# Power-Supply.net
KiCad netlist of a schematic drawn in Altium Designer
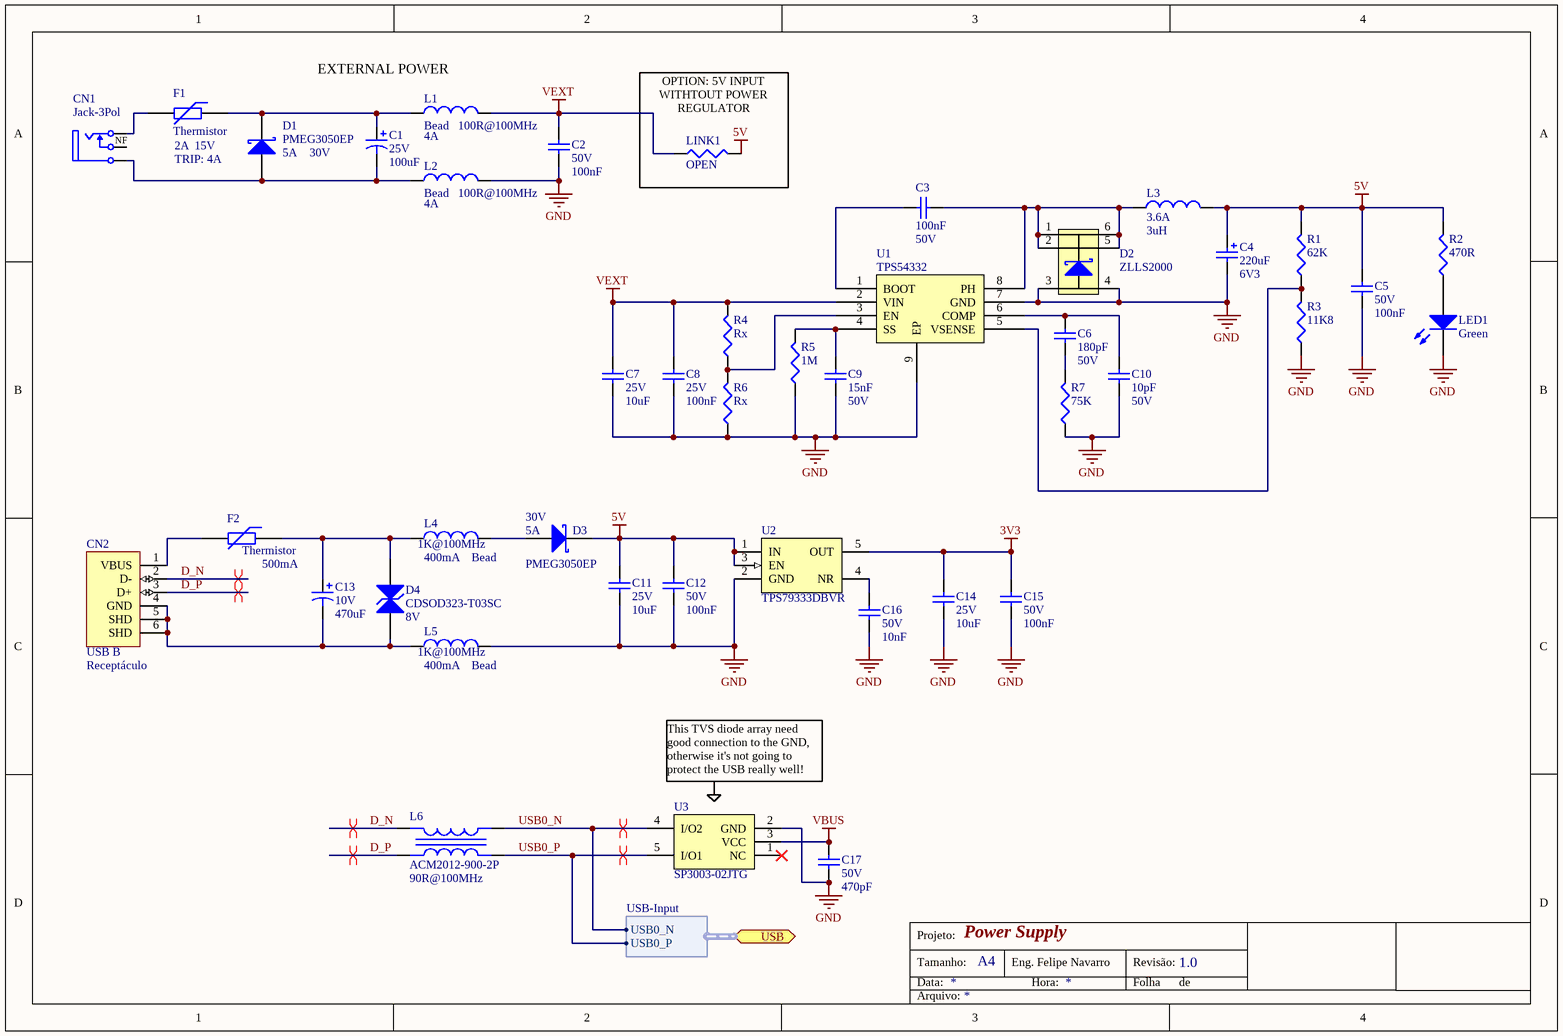
[diagram p0: Power-Supply.SchDoc]

(export (version "E")
  (design (tool "Eeschema 10.0.6"))
  (components
    (comp (ref "C1")
      (value "100uF")
      (footprint "CPOLRAD8X14")
      (description "Polarized Capacitor (Radial)")
      (fields (field (name "TENSÃO") "25V") (field (name "Comment") "Capacitor Eletrolítico"))
      (libsource (lib "NavarroCAP") (part "PCap 100uF 25V 8d.x14h."))
    )
    (comp (ref "C2")
      (value "100nF")
      (footprint "CC0603")
      (description "Capacitor (Semiconductor SIM Model)")
      (fields (field (name "TENSÃO") "50V") (field (name "Comment") "Capacitor Cerâmico"))
      (libsource (lib "NavarroCAP") (part "Cap 100nF 50V 0603 X7R"))
    )
    (comp (ref "C3")
      (value "100nF")
      (footprint "CC0603")
      (description "Capacitor (Semiconductor SIM Model)")
      (fields (field (name "TENSÃO") "50V") (field (name "Comment") "Capacitor Cerâmico"))
      (libsource (lib "NavarroCAP") (part "Cap 100nF 50V 0603 X7R"))
    )
    (comp (ref "C4")
      (value "220uF")
      (footprint "CPOL2917")
      (description "Polarized Capacitor")
      (fields (field (name "TENSÃO") "6V3") (field (name "Comment") "Capacitor Tântalo"))
      (libsource (lib "NavarroCAP") (part "PCap 220uF 6V3 2917 LOESR"))
    )
    (comp (ref "C5")
      (value "100nF")
      (footprint "CC0603")
      (description "Capacitor (Semiconductor SIM Model)")
      (fields (field (name "TENSÃO") "50V") (field (name "Comment") "Capacitor Cerâmico"))
      (libsource (lib "NavarroCAP") (part "Cap 100nF 50V 0603 X7R"))
    )
    (comp (ref "C6")
      (value "180pF")
      (footprint "CC0603")
      (description "Capacitor (Semiconductor SIM Model)")
      (fields (field (name "TENSÃO") "50V") (field (name "Comment") "Capacitor Cerâmico"))
      (libsource (lib "NavarroCAP") (part "Cap 180pF 50V 0603 NP0"))
    )
    (comp (ref "C7")
      (value "10uF")
      (footprint "CC0805")
      (description "Capacitor (Semiconductor SIM Model)")
      (fields (field (name "TENSÃO") "25V") (field (name "Comment") "Capacitor Cerâmico"))
      (libsource (lib "NavarroCAP") (part "Cap 10uF 25V 0805 X5R"))
    )
    (comp (ref "C8")
      (value "100nF")
      (footprint "CC0603")
      (description "Capacitor (Semiconductor SIM Model)")
      (fields (field (name "TENSÃO") "25V") (field (name "Comment") "Capacitor Cerâmico"))
      (libsource (lib "NavarroCAP") (part "Cap 100nF 25V 0603 X7R"))
    )
    (comp (ref "C9")
      (value "15nF")
      (footprint "CC0603")
      (description "Capacitor (Semiconductor SIM Model)")
      (fields (field (name "TENSÃO") "50V") (field (name "Comment") "Capacitor Cerâmico"))
      (libsource (lib "NavarroCAP") (part "Cap 15nF 50V 0603 X7R"))
    )
    (comp (ref "C10")
      (value "10pF")
      (footprint "CC0603")
      (description "Capacitor (Semiconductor SIM Model)")
      (fields (field (name "TENSÃO") "50V") (field (name "Comment") "Capacitor Cerâmico"))
      (libsource (lib "NavarroCAP") (part "Cap 10pF 50V 0603 NP0 5%"))
    )
    (comp (ref "C11")
      (value "10uF")
      (footprint "CC0805")
      (description "Capacitor (Semiconductor SIM Model)")
      (fields (field (name "TENSÃO") "25V") (field (name "Comment") "Capacitor Cerâmico"))
      (libsource (lib "NavarroCAP") (part "Cap 10uF 25V 0805 X5R"))
    )
    (comp (ref "C12")
      (value "100nF")
      (footprint "CC0603")
      (description "Capacitor (Semiconductor SIM Model)")
      (fields (field (name "TENSÃO") "50V") (field (name "Comment") "Capacitor Cerâmico"))
      (libsource (lib "NavarroCAP") (part "Cap 100nF 50V 0603 X7R"))
    )
    (comp (ref "C13")
      (value "470uF")
      (footprint "CPOLRAD6X12")
      (description "Polarized Capacitor (Radial)")
      (fields (field (name "TENSÃO") "10V") (field (name "Comment") "Capacitor Eletrolítico"))
      (libsource (lib "NavarroCAP") (part "PCap 470uF 10V 6d.x12h."))
    )
    (comp (ref "C14")
      (value "10uF")
      (footprint "CC0805")
      (description "Capacitor (Semiconductor SIM Model)")
      (fields (field (name "TENSÃO") "25V") (field (name "Comment") "Capacitor Cerâmico"))
      (libsource (lib "NavarroCAP") (part "Cap 10uF 25V 0805 X5R"))
    )
    (comp (ref "C15")
      (value "100nF")
      (footprint "CC0603")
      (description "Capacitor (Semiconductor SIM Model)")
      (fields (field (name "TENSÃO") "50V") (field (name "Comment") "Capacitor Cerâmico"))
      (libsource (lib "NavarroCAP") (part "Cap 100nF 50V 0603 X7R"))
    )
    (comp (ref "C16")
      (value "10nF")
      (footprint "CC0603")
      (description "Capacitor (Semiconductor SIM Model)")
      (fields (field (name "TENSÃO") "50V") (field (name "Comment") "Capacitor Cerâmico"))
      (libsource (lib "NavarroCAP") (part "Cap 10nF 50V 0603 X7R 5%"))
    )
    (comp (ref "C17")
      (value "470pF")
      (footprint "CC0603")
      (description "Capacitor (Semiconductor SIM Model)")
      (fields (field (name "TENSÃO") "50V") (field (name "Comment") "Capacitor Cerâmico"))
      (libsource (lib "NavarroCAP") (part "Cap 470pF 50V 0603 X7R"))
    )
    (comp (ref "CN1")
      (value "Jack-3Pol")
      (footprint "CONN_JACK-FONTE_3N")
      (description "Jack Socket, Thru-Hole, Vertical, 2 Conductors, 3 Contacts Single Switch, Normally Closed")
      (libsource (lib "NavarroCON") (part "Jack-3Pol"))
    )
    (comp (ref "CN2")
      (value "USB B")
      (footprint "CONN_USB-B_RCPT-H")
      (description "Conector Jack USB B, Through Hole, Right Angle, Horizontal")
      (fields (field (name "ALTIUM_VALUE") "Receptáculo"))
      (libsource (lib "NavarroCON") (part "USB B RCPT-H"))
    )
    (comp (ref "D1")
      (value "PMEG3050EP")
      (footprint "SOD-128")
      (description "Schottky Diode")
      (fields (field (name "CORRENTE") "5A") (field (name "TENSÃO") "30V"))
      (libsource (lib "NavarroSEMI") (part "DS 30V 5A SOD-128"))
    )
    (comp (ref "D2")
      (value "ZLLS2000")
      (footprint "SOT-23-6N")
      (description "Power Shottky")
      (libsource (lib "NavarroSEMI") (part "DPS 40V 2.2A SOT-23-6N"))
    )
    (comp (ref "D3")
      (value "PMEG3050EP")
      (footprint "SOD-128")
      (description "Schottky Diode")
      (fields (field (name "CORRENTE") "5A") (field (name "TENSÃO") "30V"))
      (libsource (lib "NavarroSEMI") (part "DS 30V 5A SOD-128"))
    )
    (comp (ref "D4")
      (value "CDSOD323-T03SC")
      (footprint "SOD-323 BIDIRECT")
      (description "Transient Voltage Supressor diode")
      (fields (field (name "TENSÃO") "8V"))
      (libsource (lib "NavarroSEMI") (part "TVS 8V 5% SOD323 BI 400W"))
    )
    (comp (ref "F1")
      (value "Thermistor")
      (footprint "CC1210")
      (description "Varistor (Voltage-Sensitive Resistor)")
      (fields (field (name "CORRENTE") "2A") (field (name "TENSÃO") "15V") (field (name "OBS") "TRIP: 4A"))
      (libsource (lib "Miscellaneous Devices") (part "Res Varistor"))
    )
    (comp (ref "F2")
      (value "Thermistor")
      (footprint "CC1812")
      (description "Varistor (Voltage-Sensitive Resistor)")
      (fields (field (name "CORRENTE") "500mA"))
      (libsource (lib "Miscellaneous Devices") (part "Res Varistor"))
    )
    (comp (ref "L1")
      (value "Bead")
      (footprint "CC0805")
      (fields (field (name "CORRENTE") "4A") (field (name "ALTIUM_VALUE") "100R@100MHz"))
      (libsource (lib "NavarroIND") (part "Bd 180R@100MHz 1806 3A"))
    )
    (comp (ref "L2")
      (value "Bead")
      (footprint "CC0805")
      (fields (field (name "CORRENTE") "4A") (field (name "ALTIUM_VALUE") "100R@100MHz"))
      (libsource (lib "NavarroIND") (part "Bd 180R@100MHz 1806 3A"))
    )
    (comp (ref "L3")
      (value "3uH")
      (footprint "NR2424")
      (description "Inductor")
      (fields (field (name "CORRENTE") "3.6A") (field (name "Comment") "Indutor"))
      (libsource (lib "NavarroIND") (part "Ind 3uH 2424 3.6A"))
    )
    (comp (ref "L4")
      (value "Bead")
      (footprint "CC0603")
      (fields (field (name "CORRENTE") "400mA") (field (name "ALTIUM_VALUE") "1K@100MHz"))
      (libsource (lib "NavarroIND") (part "Bd 1K@100MHz 0603 400mA"))
    )
    (comp (ref "L5")
      (value "Bead")
      (footprint "CC0603")
      (fields (field (name "CORRENTE") "400mA") (field (name "ALTIUM_VALUE") "1K@100MHz"))
      (libsource (lib "NavarroIND") (part "Bd 1K@100MHz 0603 400mA"))
    )
    (comp (ref "L6")
      (value "ACM2012-900-2P")
      (footprint "TR0805-4N")
      (description "Indutor de Modo Comum")
      (fields (field (name "ALTIUM_VALUE") "90R@100MHz"))
      (libsource (lib "NavarroIND") (part "MC 90R@100MHz 0805 0.4A"))
    )
    (comp (ref "LED1")
      (value "Green")
      (footprint "LED-INDIC")
      (description "Typical RED, GREEN, YELLOW, AMBER GaAs LED")
      (fields (field (name "Comment") "LED"))
      (libsource (lib "Miscellaneous Devices") (part "LED2"))
    )
    (comp (ref "LINK1")
      (value "OPEN")
      (footprint "CC1210")
      (description "Resistor")
      (fields (field (name "Comment") "Resistor Open"))
      (libsource (lib "NavarroRES") (part "Res Open 0603"))
    )
    (comp (ref "R1")
      (value "62K")
      (footprint "CC0603")
      (description "Resistor")
      (libsource (lib "NavarroRES") (part "Res 62K 1% 0603 1/10W"))
    )
    (comp (ref "R2")
      (value "470R")
      (footprint "CC0603")
      (description "Resistor")
      (libsource (lib "NavarroRES") (part "Res 470R 5% 0603 1/10W"))
    )
    (comp (ref "R3")
      (value "11K8")
      (footprint "CC0603")
      (description "Resistor")
      (libsource (lib "NavarroRES") (part "Res 11K8 1% 0603 1/10W"))
    )
    (comp (ref "R4")
      (value "Rx")
      (footprint "CC0603")
      (description "Resistor")
      (libsource (lib "NavarroRES") (part "Res 150K 1% 0603 1/10W"))
    )
    (comp (ref "R5")
      (value "1M")
      (footprint "CC0603")
      (description "Resistor")
      (libsource (lib "NavarroRES") (part "Res 1M 1% 0603 1/10W"))
    )
    (comp (ref "R6")
      (value "Rx")
      (footprint "CC0603")
      (description "Resistor")
      (libsource (lib "NavarroRES") (part "Res 48K7 1% 0603 1/10W"))
    )
    (comp (ref "R7")
      (value "75K")
      (footprint "CC0603")
      (description "Resistor")
      (libsource (lib "NavarroRES") (part "Res 75K 1% 0603 1/10W"))
    )
    (comp (ref "U1")
      (value "TPS54332")
      (footprint "SOIC-8N-EP")
      (description "DC/DC Converter Step-Down 3.5A 28V")
      (libsource (lib "Navarro") (part "TPS54332"))
    )
    (comp (ref "U2")
      (value "TPS79333DBVR")
      (footprint "SOT-23-5N")
      (description "ULTRALOW-NOISE, HIGH PSRR, FAST RF 200mA LOW-DROPOUT LINEAR  REGULATORS I")
      (libsource (lib "Navarro") (part "TPS79333"))
    )
    (comp (ref "U3")
      (value "SP3003-02JTG")
      (footprint "Tecnoclade:SC70-5N")
      (description "TVS DIODE ARRAY")
      (libsource (lib "NavarroSEMI") (part "SP3003-02JTG"))
    )
  )
  (nets
    (net (code "2") (name "/D_N") (class "Default")
      (node (ref "CN2") (pin "2") (pinfunction "D-_2") (pintype "bidirectional"))
      (node (ref "L6") (pin "1") (pinfunction "Pri+_1") (pintype "passive"))
    )
    (net (code "3") (name "/D_P") (class "Default")
      (node (ref "CN2") (pin "3") (pinfunction "D+_3") (pintype "bidirectional"))
      (node (ref "L6") (pin "2") (pinfunction "Pri-_2") (pintype "passive"))
    )
    (net (code "4") (name "/USB0_N") (class "Default")
      (node (ref "L6") (pin "4") (pinfunction "Sec-_4") (pintype "passive"))
      (node (ref "U3") (pin "4") (pinfunction "I/O2_4") (pintype "passive"))
    )
    (net (code "5") (name "/USB0_P") (class "Default")
      (node (ref "L6") (pin "3") (pinfunction "Sec+_3") (pintype "passive"))
      (node (ref "U3") (pin "5") (pinfunction "I/O1_5") (pintype "passive"))
    )
    (net (code "7") (name "3V3") (class "Default")
      (node (ref "C14") (pin "2") (pinfunction "2_2") (pintype "passive"))
      (node (ref "C15") (pin "2") (pinfunction "2_2") (pintype "passive"))
      (node (ref "U2") (pin "5") (pinfunction "OUT_5") (pintype "power_in"))
    )
    (net (code "8") (name "5V") (class "Default")
      (node (ref "C11") (pin "2") (pinfunction "2_2") (pintype "passive"))
      (node (ref "C12") (pin "2") (pinfunction "2_2") (pintype "passive"))
      (node (ref "C4") (pin "1") (pinfunction "1_1") (pintype "passive"))
      (node (ref "C5") (pin "2") (pinfunction "2_2") (pintype "passive"))
      (node (ref "D3") (pin "2") (pinfunction "K_2") (pintype "passive"))
      (node (ref "L3") (pin "2") (pinfunction "2_2") (pintype "passive"))
      (node (ref "LINK1") (pin "2") (pinfunction "2_2") (pintype "passive"))
      (node (ref "R1") (pin "2") (pinfunction "2_2") (pintype "passive"))
      (node (ref "R2") (pin "2") (pinfunction "2_2") (pintype "passive"))
      (node (ref "U2") (pin "1") (pinfunction "IN_1") (pintype "power_in"))
      (node (ref "U2") (pin "3") (pinfunction "EN_3") (pintype "input"))
    )
    (net (code "9") (name "GND") (class "Default")
      (node (ref "C10") (pin "1") (pinfunction "1_1") (pintype "passive"))
      (node (ref "C11") (pin "1") (pinfunction "1_1") (pintype "passive"))
      (node (ref "C12") (pin "1") (pinfunction "1_1") (pintype "passive"))
      (node (ref "C14") (pin "1") (pinfunction "1_1") (pintype "passive"))
      (node (ref "C15") (pin "1") (pinfunction "1_1") (pintype "passive"))
      (node (ref "C16") (pin "1") (pinfunction "1_1") (pintype "passive"))
      (node (ref "C17") (pin "1") (pinfunction "1_1") (pintype "passive"))
      (node (ref "C2") (pin "1") (pinfunction "1_1") (pintype "passive"))
      (node (ref "C4") (pin "2") (pinfunction "2_2") (pintype "passive"))
      (node (ref "C5") (pin "1") (pinfunction "1_1") (pintype "passive"))
      (node (ref "C7") (pin "1") (pinfunction "1_1") (pintype "passive"))
      (node (ref "C8") (pin "1") (pinfunction "1_1") (pintype "passive"))
      (node (ref "C9") (pin "1") (pinfunction "1_1") (pintype "passive"))
      (node (ref "D2") (pin "3") (pinfunction "A_3") (pintype "passive"))
      (node (ref "D2") (pin "4") (pinfunction "A_4") (pintype "passive"))
      (node (ref "L2") (pin "2") (pinfunction "2_2") (pintype "passive"))
      (node (ref "L5") (pin "2") (pinfunction "2_2") (pintype "passive"))
      (node (ref "LED1") (pin "2") (pinfunction "K_2") (pintype "passive"))
      (node (ref "R3") (pin "1") (pinfunction "1_1") (pintype "passive"))
      (node (ref "R5") (pin "1") (pinfunction "1_1") (pintype "passive"))
      (node (ref "R6") (pin "1") (pinfunction "1_1") (pintype "passive"))
      (node (ref "R7") (pin "1") (pinfunction "1_1") (pintype "passive"))
      (node (ref "U1") (pin "7") (pinfunction "GND_7") (pintype "passive"))
      (node (ref "U1") (pin "9") (pinfunction "EP_9") (pintype "passive"))
      (node (ref "U2") (pin "2") (pinfunction "GND_2") (pintype "power_in"))
      (node (ref "U3") (pin "2") (pinfunction "GND_2") (pintype "passive"))
    )
    (net (code "10") (name "Net-(C6-Pad1)") (class "Default")
      (node (ref "C6") (pin "1") (pinfunction "1_1") (pintype "passive"))
      (node (ref "R7") (pin "2") (pinfunction "2_2") (pintype "passive"))
    )
    (net (code "11") (name "Net-(CN1-Centro)") (class "Default")
      (node (ref "CN1") (pin "1") (pinfunction "Centro_1") (pintype "power_in"))
      (node (ref "F1") (pin "2") (pinfunction "2_2") (pintype "passive"))
    )
    (net (code "12") (name "Net-(CN1-Malha)") (class "Default")
      (node (ref "C1") (pin "2") (pinfunction "2_2") (pintype "passive"))
      (node (ref "CN1") (pin "2") (pinfunction "Malha_2") (pintype "power_in"))
      (node (ref "D1") (pin "1") (pinfunction "A_1") (pintype "passive"))
      (node (ref "L2") (pin "1") (pinfunction "1_1") (pintype "passive"))
    )
    (net (code "13") (name "Net-(CN2-GND)") (class "Default")
      (node (ref "C13") (pin "2") (pinfunction "2_2") (pintype "passive"))
      (node (ref "CN2") (pin "4") (pinfunction "GND_4") (pintype "power_in"))
      (node (ref "CN2") (pin "5") (pinfunction "SHD_5") (pintype "passive"))
      (node (ref "CN2") (pin "6") (pinfunction "SHD_6") (pintype "passive"))
      (node (ref "D4") (pin "1") (pinfunction "A_1") (pintype "passive"))
      (node (ref "L5") (pin "1") (pinfunction "1_1") (pintype "passive"))
    )
    (net (code "14") (name "Net-(CN2-VBUS)") (class "Default")
      (node (ref "CN2") (pin "1") (pinfunction "VBUS_1") (pintype "power_in"))
      (node (ref "F2") (pin "2") (pinfunction "2_2") (pintype "passive"))
    )
    (net (code "15") (name "Net-(D1-K)") (class "Default")
      (node (ref "C1") (pin "1") (pinfunction "1_1") (pintype "passive"))
      (node (ref "D1") (pin "2") (pinfunction "K_2") (pintype "passive"))
      (node (ref "F1") (pin "1") (pinfunction "1_1") (pintype "passive"))
      (node (ref "L1") (pin "1") (pinfunction "1_1") (pintype "passive"))
    )
    (net (code "16") (name "Net-(D3-A)") (class "Default")
      (node (ref "D3") (pin "1") (pinfunction "A_1") (pintype "passive"))
      (node (ref "L4") (pin "2") (pinfunction "2_2") (pintype "passive"))
    )
    (net (code "17") (name "Net-(D4-K)") (class "Default")
      (node (ref "C13") (pin "1") (pinfunction "1_1") (pintype "passive"))
      (node (ref "D4") (pin "2") (pinfunction "K_2") (pintype "passive"))
      (node (ref "F2") (pin "1") (pinfunction "1_1") (pintype "passive"))
      (node (ref "L4") (pin "1") (pinfunction "1_1") (pintype "passive"))
    )
    (net (code "18") (name "Net-(LED1-A)") (class "Default")
      (node (ref "LED1") (pin "1") (pinfunction "A_1") (pintype "passive"))
      (node (ref "R2") (pin "1") (pinfunction "1_1") (pintype "passive"))
    )
    (net (code "19") (name "Net-(U1-BOOT)") (class "Default")
      (node (ref "C3") (pin "2") (pinfunction "2_2") (pintype "passive"))
      (node (ref "U1") (pin "1") (pinfunction "BOOT_1") (pintype "passive"))
    )
    (net (code "20") (name "Net-(U1-COMP)") (class "Default")
      (node (ref "C10") (pin "2") (pinfunction "2_2") (pintype "passive"))
      (node (ref "C6") (pin "2") (pinfunction "2_2") (pintype "passive"))
      (node (ref "U1") (pin "6") (pinfunction "COMP_6") (pintype "passive"))
    )
    (net (code "21") (name "Net-(U1-EN)") (class "Default")
      (node (ref "R4") (pin "1") (pinfunction "1_1") (pintype "passive"))
      (node (ref "R6") (pin "2") (pinfunction "2_2") (pintype "passive"))
      (node (ref "U1") (pin "3") (pinfunction "EN_3") (pintype "passive"))
    )
    (net (code "22") (name "Net-(U1-PH)") (class "Default")
      (node (ref "C3") (pin "1") (pinfunction "1_1") (pintype "passive"))
      (node (ref "D2") (pin "1") (pinfunction "C_1") (pintype "passive"))
      (node (ref "D2") (pin "2") (pinfunction "C_2") (pintype "passive"))
      (node (ref "D2") (pin "5") (pinfunction "C_5") (pintype "passive"))
      (node (ref "D2") (pin "6") (pinfunction "C_6") (pintype "passive"))
      (node (ref "L3") (pin "1") (pinfunction "1_1") (pintype "passive"))
      (node (ref "U1") (pin "8") (pinfunction "PH_8") (pintype "passive"))
    )
    (net (code "23") (name "Net-(U1-SS)") (class "Default")
      (node (ref "C9") (pin "2") (pinfunction "2_2") (pintype "passive"))
      (node (ref "R5") (pin "2") (pinfunction "2_2") (pintype "passive"))
      (node (ref "U1") (pin "4") (pinfunction "SS_4") (pintype "passive"))
    )
    (net (code "24") (name "Net-(U1-VSENSE)") (class "Default")
      (node (ref "R1") (pin "1") (pinfunction "1_1") (pintype "passive"))
      (node (ref "R3") (pin "2") (pinfunction "2_2") (pintype "passive"))
      (node (ref "U1") (pin "5") (pinfunction "VSENSE_5") (pintype "passive"))
    )
    (net (code "25") (name "Net-(U2-NR)") (class "Default")
      (node (ref "C16") (pin "2") (pinfunction "2_2") (pintype "passive"))
      (node (ref "U2") (pin "4") (pinfunction "NR_4") (pintype "passive"))
    )
    (net (code "26") (name "VBUS") (class "Default")
      (node (ref "C17") (pin "2") (pinfunction "2_2") (pintype "passive"))
      (node (ref "U3") (pin "3") (pinfunction "VCC_3") (pintype "passive"))
    )
    (net (code "27") (name "VEXT") (class "Default")
      (node (ref "C2") (pin "2") (pinfunction "2_2") (pintype "passive"))
      (node (ref "C7") (pin "2") (pinfunction "2_2") (pintype "passive"))
      (node (ref "C8") (pin "2") (pinfunction "2_2") (pintype "passive"))
      (node (ref "L1") (pin "2") (pinfunction "2_2") (pintype "passive"))
      (node (ref "LINK1") (pin "1") (pinfunction "1_1") (pintype "passive"))
      (node (ref "R4") (pin "2") (pinfunction "2_2") (pintype "passive"))
      (node (ref "U1") (pin "2") (pinfunction "VIN_2") (pintype "passive"))
    )
    (net (code "28") (name "unconnected-(CN1-NF-Pad3)") (class "Default")
      (node (ref "CN1") (pin "3") (pinfunction "NF_3") (pintype "passive"))
    )
    (net (code "29") (name "unconnected-(U3-NC-Pad1)") (class "Default")
      (node (ref "U3") (pin "1") (pinfunction "NC_1") (pintype "passive+no_connect"))
    )
  )
)
